# LPEM.net
KiCad netlist of a schematic drawn in EAGLE
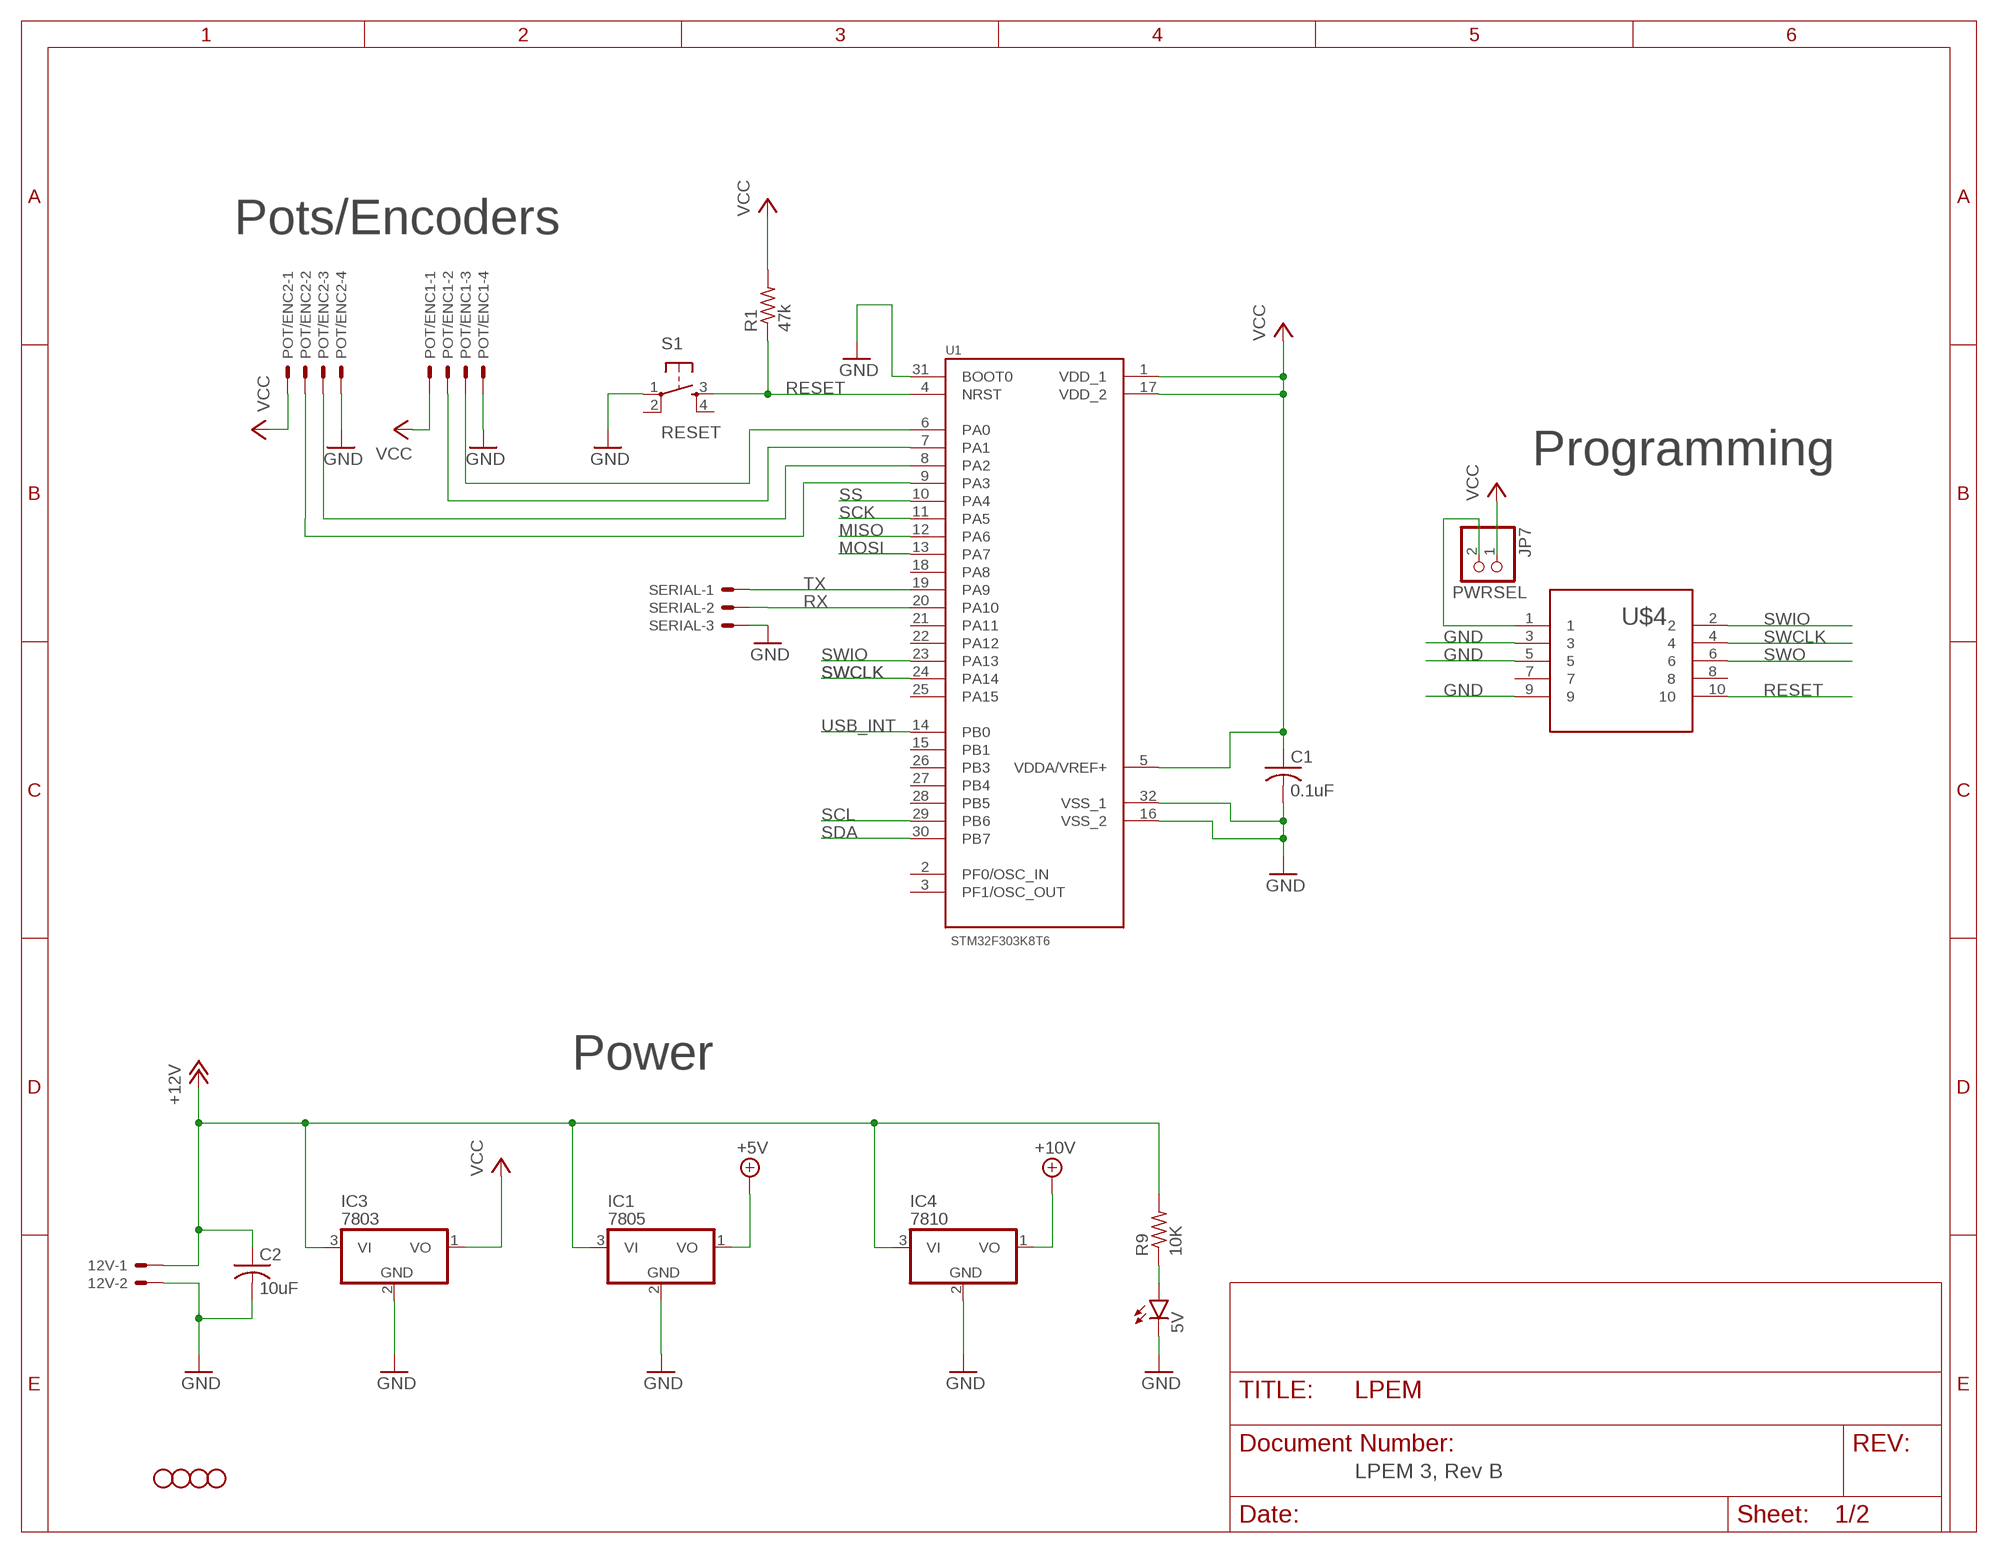
[diagram p0: schematic, sheet 1]
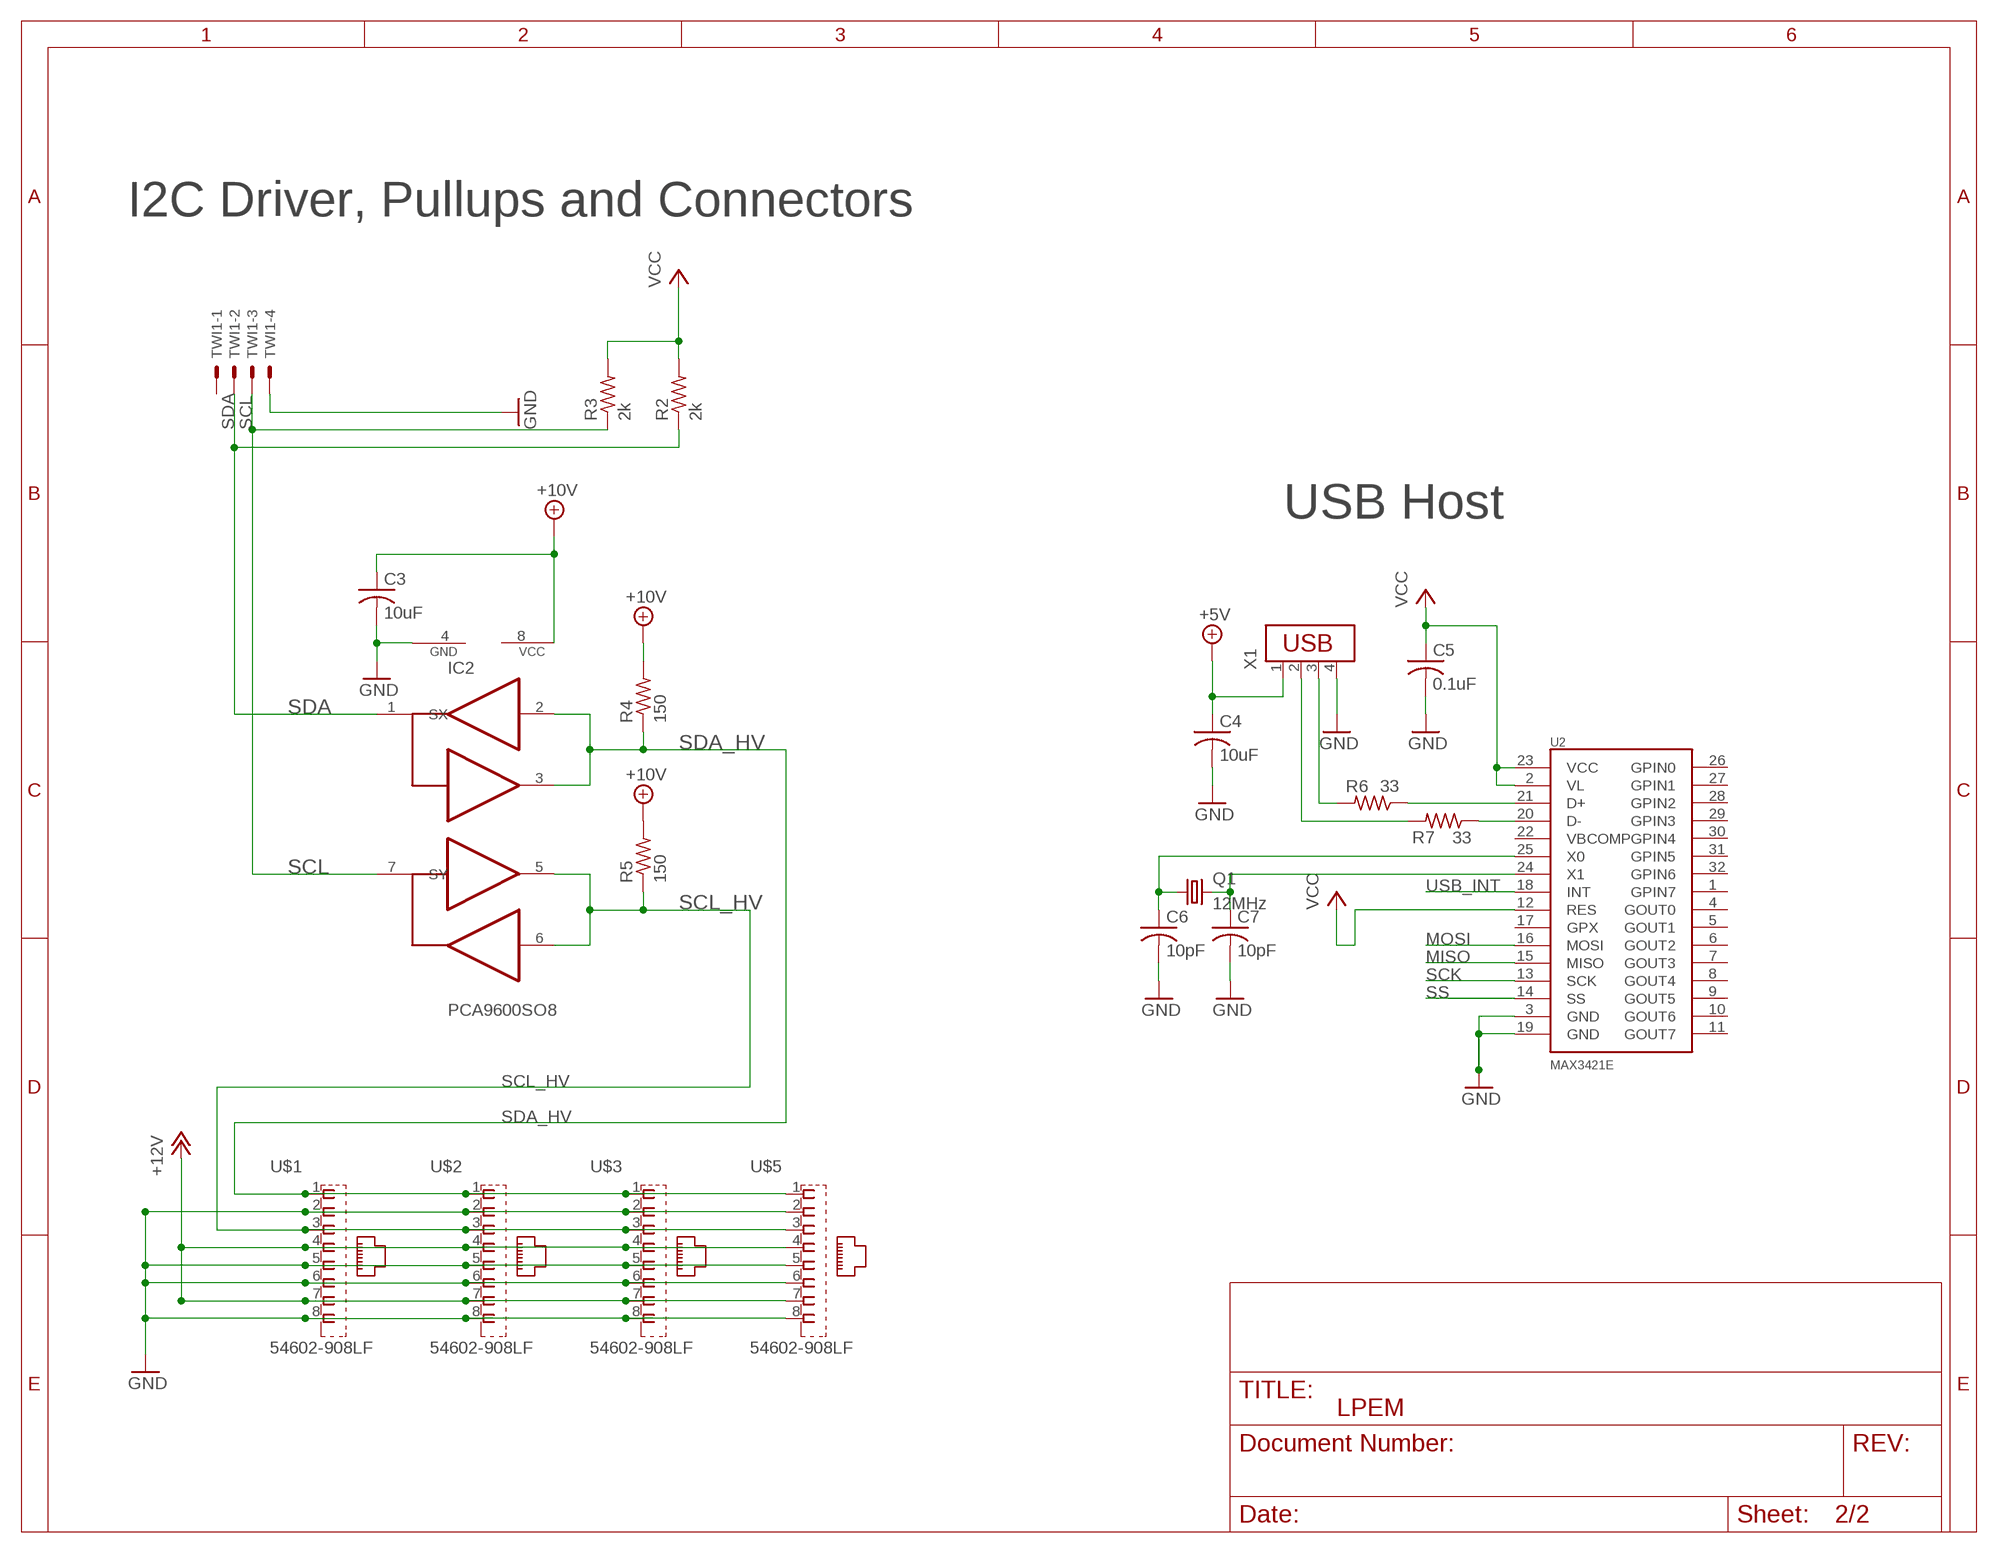
[diagram p1: schematic, sheet 2]

(export (version "E")
  (design (tool "Eeschema 10.0.6"))
  (components
    (comp (ref "C3")
      (value "10uF")
      (footprint "eagle-import:C025-025X050")
      (libsource (lib "eagle-import") (part "C-US025-025X050"))
    )
    (comp (ref "C4")
      (value "10uF")
      (footprint "eagle-import:C025-025X050")
      (libsource (lib "eagle-import") (part "C-US025-025X050"))
    )
    (comp (ref "C5")
      (value "0.1uF")
      (footprint "eagle-import:C025-025X050")
      (libsource (lib "eagle-import") (part "C-US025-025X050"))
    )
    (comp (ref "C6")
      (value "10pF")
      (footprint "eagle-import:C025-025X050")
      (libsource (lib "eagle-import") (part "C-US025-025X050"))
    )
    (comp (ref "C7")
      (value "10pF")
      (footprint "eagle-import:C025-025X050")
      (libsource (lib "eagle-import") (part "C-US025-025X050"))
    )
    (comp (ref "IC2")
      (value "PCA9600SO8")
      (footprint "eagle-import:SO08")
      (libsource (lib "eagle-import") (part "PCA9600SO8"))
    )
    (comp (ref "Q1")
      (value "12MHz")
      (footprint "eagle-import:HC18U-V")
      (libsource (lib "eagle-import") (part "CRYSTALHC18U-V"))
    )
    (comp (ref "R2")
      (value "2k")
      (footprint "eagle-import:0204_5")
      (libsource (lib "eagle-import") (part "R-US_0204/5"))
    )
    (comp (ref "R3")
      (value "2k")
      (footprint "eagle-import:0204_5")
      (libsource (lib "eagle-import") (part "R-US_0204/5"))
    )
    (comp (ref "R4")
      (value "150")
      (footprint "eagle-import:0204_5")
      (libsource (lib "eagle-import") (part "R-US_0204/5"))
    )
    (comp (ref "R5")
      (value "150")
      (footprint "eagle-import:0204_5")
      (libsource (lib "eagle-import") (part "R-US_0204/5"))
    )
    (comp (ref "R6")
      (value "33")
      (footprint "eagle-import:0204_5")
      (libsource (lib "eagle-import") (part "R-US_0204/5"))
    )
    (comp (ref "R7")
      (value "33")
      (footprint "eagle-import:0204_5")
      (libsource (lib "eagle-import") (part "R-US_0204/5"))
    )
    (comp (ref "TWI1")
      (value "22-23-2041")
      (footprint "eagle-import:22-23-2041")
      (fields (field (name "MF") "MOLEX"))
      (libsource (lib "eagle-import") (part "22-23-2041"))
    )
    (comp (ref "U$1")
      (value "54602-908LF")
      (footprint "eagle-import:AMPHENOL_54602-908LF")
      (fields (field (name "DIGI-KEY_PART_NUMBER") "609-1046-ND") (field (name "MF") "Amphenol ICC"))
      (libsource (lib "eagle-import") (part "54602-908LF"))
    )
    (comp (ref "U$2")
      (value "54602-908LF")
      (footprint "eagle-import:AMPHENOL_54602-908LF")
      (fields (field (name "DIGI-KEY_PART_NUMBER") "609-1046-ND") (field (name "MF") "Amphenol ICC"))
      (libsource (lib "eagle-import") (part "54602-908LF"))
    )
    (comp (ref "U$3")
      (value "54602-908LF")
      (footprint "eagle-import:AMPHENOL_54602-908LF")
      (fields (field (name "DIGI-KEY_PART_NUMBER") "609-1046-ND") (field (name "MF") "Amphenol ICC"))
      (libsource (lib "eagle-import") (part "54602-908LF"))
    )
    (comp (ref "U$5")
      (value "54602-908LF")
      (footprint "eagle-import:AMPHENOL_54602-908LF")
      (fields (field (name "DIGI-KEY_PART_NUMBER") "609-1046-ND") (field (name "MF") "Amphenol ICC"))
      (libsource (lib "eagle-import") (part "54602-908LF"))
    )
    (comp (ref "U2")
      (value "MAX3421E")
      (footprint "eagle-import:TQFP32-5MM")
      (fields (field (name "MF") "Maxim Integrated"))
      (libsource (lib "eagle-import") (part "MAX3421E"))
    )
    (comp (ref "X1")
      (value "USB-787616")
      (footprint "eagle-import:USB")
      (libsource (lib "eagle-import") (part "USB-787616"))
    )
    (comp (ref "5V")
      (value "LED3MM")
      (footprint "eagle-import:LED3MM")
      (libsource (lib "eagle-import") (part "LED3MM"))
    )
    (comp (ref "12V")
      (value "22-23-2021")
      (footprint "eagle-import:22-23-2021")
      (fields (field (name "MF") "MOLEX"))
      (libsource (lib "eagle-import") (part "22-23-2021"))
    )
    (comp (ref "C1")
      (value "0.1uF")
      (footprint "eagle-import:C025-025X050")
      (libsource (lib "eagle-import") (part "C-US025-025X050"))
    )
    (comp (ref "C2")
      (value "10uF")
      (footprint "eagle-import:C025-025X050")
      (libsource (lib "eagle-import") (part "C-US025-025X050"))
    )
    (comp (ref "IC1")
      (value "7805")
      (footprint "eagle-import:TO92")
      (libsource (lib "eagle-import") (part "78ZL05"))
    )
    (comp (ref "IC3")
      (value "7803")
      (footprint "eagle-import:TO92")
      (libsource (lib "eagle-import") (part "78ZL05"))
    )
    (comp (ref "IC4")
      (value "7810")
      (footprint "eagle-import:TO92")
      (libsource (lib "eagle-import") (part "78ZL05"))
    )
    (comp (ref "JP1")
      (value "STAND-OFF")
      (footprint "eagle-import:STAND-OFF")
      (libsource (lib "eagle-import") (part "STAND-OFF"))
    )
    (comp (ref "JP2")
      (value "STAND-OFF")
      (footprint "eagle-import:STAND-OFF")
      (libsource (lib "eagle-import") (part "STAND-OFF"))
    )
    (comp (ref "JP7")
      (value "PWRSEL")
      (footprint "eagle-import:1X02")
      (libsource (lib "eagle-import") (part "PINHD-1X2"))
    )
    (comp (ref "JP8")
      (value "STAND-OFF")
      (footprint "eagle-import:STAND-OFF")
      (libsource (lib "eagle-import") (part "STAND-OFF"))
    )
    (comp (ref "JP9")
      (value "STAND-OFF")
      (footprint "eagle-import:STAND-OFF")
      (libsource (lib "eagle-import") (part "STAND-OFF"))
    )
    (comp (ref "POT/ENC1")
      (value "22-23-2041")
      (footprint "eagle-import:22-23-2041")
      (fields (field (name "MF") "MOLEX"))
      (libsource (lib "eagle-import") (part "22-23-2041"))
    )
    (comp (ref "POT/ENC2")
      (value "22-23-2041")
      (footprint "eagle-import:22-23-2041")
      (fields (field (name "MF") "MOLEX"))
      (libsource (lib "eagle-import") (part "22-23-2041"))
    )
    (comp (ref "R1")
      (value "47k")
      (footprint "eagle-import:0204_5")
      (libsource (lib "eagle-import") (part "R-US_0204/5"))
    )
    (comp (ref "R9")
      (value "10K")
      (footprint "eagle-import:0204_5")
      (libsource (lib "eagle-import") (part "R-US_0204/5"))
    )
    (comp (ref "S1")
      (value "RESET")
      (footprint "eagle-import:TACTILE-PTH")
      (libsource (lib "eagle-import") (part "TAC_SWITCHPTH"))
    )
    (comp (ref "SERIAL")
      (value "22-23-2031")
      (footprint "eagle-import:22-23-2031")
      (fields (field (name "MF") "MOLEX"))
      (libsource (lib "eagle-import") (part "22-23-2031"))
    )
    (comp (ref "U$4")
      (value "CORTEX_HEADERJ")
      (footprint "eagle-import:CORTEX_HEADER")
      (fields (field (name "MF") "Samtec Inc.") (field (name "MP") "TFM-105-01-S-D-WT"))
      (libsource (lib "eagle-import") (part "CORTEX_HEADERJ"))
    )
    (comp (ref "U1")
      (value "STM32F303K8T6")
      (footprint "eagle-import:QFP80P900X900X160-32N")
      (fields (field (name "MF") "STMicroelectronics"))
      (libsource (lib "eagle-import") (part "STM32F303K8T6"))
    )
  )
  (nets
    (net (code "1") (name "+5V") (class "Default")
      (node (ref "C4") (pin "1") (pinfunction "1_1") (pintype "passive"))
      (node (ref "IC1") (pin "1") (pinfunction "VO_1") (pintype "passive"))
      (node (ref "X1") (pin "1") (pinfunction "1_1") (pintype "passive"))
    )
    (net (code "2") (name "+10V") (class "Default")
      (node (ref "C3") (pin "1") (pinfunction "1_1") (pintype "passive"))
      (node (ref "IC2") (pin "8") (pinfunction "VCC_8") (pintype "power_in"))
      (node (ref "IC4") (pin "1") (pinfunction "VO_1") (pintype "passive"))
      (node (ref "R4") (pin "2") (pinfunction "2_2") (pintype "passive"))
      (node (ref "R5") (pin "2") (pinfunction "2_2") (pintype "passive"))
    )
    (net (code "3") (name "+12V") (class "Default")
      (node (ref "12V") (pin "1") (pinfunction "S_1") (pintype "passive"))
      (node (ref "C2") (pin "1") (pinfunction "1_1") (pintype "passive"))
      (node (ref "IC1") (pin "3") (pinfunction "VI_3") (pintype "input"))
      (node (ref "IC3") (pin "3") (pinfunction "VI_3") (pintype "input"))
      (node (ref "IC4") (pin "3") (pinfunction "VI_3") (pintype "input"))
      (node (ref "R9") (pin "2") (pinfunction "2_2") (pintype "passive"))
      (node (ref "U$1") (pin "4") (pinfunction "4_4") (pintype "passive"))
      (node (ref "U$1") (pin "7") (pinfunction "7_7") (pintype "passive"))
      (node (ref "U$2") (pin "4") (pinfunction "4_4") (pintype "passive"))
      (node (ref "U$2") (pin "7") (pinfunction "7_7") (pintype "passive"))
      (node (ref "U$3") (pin "4") (pinfunction "4_4") (pintype "passive"))
      (node (ref "U$3") (pin "7") (pinfunction "7_7") (pintype "passive"))
      (node (ref "U$5") (pin "4") (pinfunction "4_4") (pintype "passive"))
      (node (ref "U$5") (pin "7") (pinfunction "7_7") (pintype "passive"))
    )
    (net (code "4") (name "GND") (class "Default")
      (node (ref "12V") (pin "2") (pinfunction "S_2") (pintype "passive"))
      (node (ref "5V") (pin "K") (pinfunction "C_K") (pintype "passive"))
      (node (ref "C1") (pin "2") (pinfunction "2_2") (pintype "passive"))
      (node (ref "C2") (pin "2") (pinfunction "2_2") (pintype "passive"))
      (node (ref "C3") (pin "2") (pinfunction "2_2") (pintype "passive"))
      (node (ref "C4") (pin "2") (pinfunction "2_2") (pintype "passive"))
      (node (ref "C5") (pin "2") (pinfunction "2_2") (pintype "passive"))
      (node (ref "C6") (pin "2") (pinfunction "2_2") (pintype "passive"))
      (node (ref "C7") (pin "2") (pinfunction "2_2") (pintype "passive"))
      (node (ref "IC1") (pin "2") (pinfunction "GND_2") (pintype "passive"))
      (node (ref "IC2") (pin "4") (pinfunction "GND_4") (pintype "power_in"))
      (node (ref "IC3") (pin "2") (pinfunction "GND_2") (pintype "passive"))
      (node (ref "IC4") (pin "2") (pinfunction "GND_2") (pintype "passive"))
      (node (ref "POT/ENC1") (pin "4") (pinfunction "S_4") (pintype "passive"))
      (node (ref "POT/ENC2") (pin "4") (pinfunction "S_4") (pintype "passive"))
      (node (ref "S1") (pin "1") (pinfunction "1_1") (pintype "passive"))
      (node (ref "SERIAL") (pin "3") (pinfunction "S_3") (pintype "passive"))
      (node (ref "TWI1") (pin "4") (pinfunction "S_4") (pintype "passive"))
      (node (ref "U$1") (pin "2") (pinfunction "2_2") (pintype "passive"))
      (node (ref "U$1") (pin "5") (pinfunction "5_5") (pintype "passive"))
      (node (ref "U$1") (pin "6") (pinfunction "6_6") (pintype "passive"))
      (node (ref "U$1") (pin "8") (pinfunction "8_8") (pintype "passive"))
      (node (ref "U$2") (pin "2") (pinfunction "2_2") (pintype "passive"))
      (node (ref "U$2") (pin "5") (pinfunction "5_5") (pintype "passive"))
      (node (ref "U$2") (pin "6") (pinfunction "6_6") (pintype "passive"))
      (node (ref "U$2") (pin "8") (pinfunction "8_8") (pintype "passive"))
      (node (ref "U$3") (pin "2") (pinfunction "2_2") (pintype "passive"))
      (node (ref "U$3") (pin "5") (pinfunction "5_5") (pintype "passive"))
      (node (ref "U$3") (pin "6") (pinfunction "6_6") (pintype "passive"))
      (node (ref "U$3") (pin "8") (pinfunction "8_8") (pintype "passive"))
      (node (ref "U$4") (pin "3") (pinfunction "3_3") (pintype "passive"))
      (node (ref "U$4") (pin "5") (pinfunction "5_5") (pintype "passive"))
      (node (ref "U$4") (pin "9") (pinfunction "9_9") (pintype "passive"))
      (node (ref "U$5") (pin "2") (pinfunction "2_2") (pintype "passive"))
      (node (ref "U$5") (pin "5") (pinfunction "5_5") (pintype "passive"))
      (node (ref "U$5") (pin "6") (pinfunction "6_6") (pintype "passive"))
      (node (ref "U$5") (pin "8") (pinfunction "8_8") (pintype "passive"))
      (node (ref "U1") (pin "16") (pinfunction "VSS_2_16") (pintype "power_in"))
      (node (ref "U1") (pin "31") (pinfunction "BOOT0_31") (pintype "input"))
      (node (ref "U1") (pin "32") (pinfunction "VSS_1_32") (pintype "power_in"))
      (node (ref "U2") (pin "19") (pinfunction "GND_19") (pintype "bidirectional"))
      (node (ref "U2") (pin "3") (pinfunction "GND_3") (pintype "bidirectional"))
      (node (ref "X1") (pin "4") (pinfunction "4_4") (pintype "passive"))
    )
    (net (code "5") (name "MISO") (class "Default")
      (node (ref "U1") (pin "12") (pinfunction "PA6_12") (pintype "bidirectional"))
      (node (ref "U2") (pin "15") (pinfunction "MISO_15") (pintype "bidirectional"))
    )
    (net (code "6") (name "MOSI") (class "Default")
      (node (ref "U1") (pin "13") (pinfunction "PA7_13") (pintype "bidirectional"))
      (node (ref "U2") (pin "16") (pinfunction "MOSI_16") (pintype "bidirectional"))
    )
    (net (code "7") (name "Net-(5V-PadA)") (class "Default")
      (node (ref "5V") (pin "A") (pinfunction "A_A") (pintype "passive"))
      (node (ref "R9") (pin "1") (pinfunction "1_1") (pintype "passive"))
    )
    (net (code "8") (name "Net-(JP7-Pad2)") (class "Default")
      (node (ref "JP7") (pin "2") (pinfunction "2_2") (pintype "passive"))
      (node (ref "U$4") (pin "1") (pinfunction "1_1") (pintype "passive"))
    )
    (net (code "9") (name "Net-(POT/ENC1B-S)") (class "Default")
      (node (ref "POT/ENC1") (pin "2") (pinfunction "S_2") (pintype "passive"))
      (node (ref "U1") (pin "7") (pinfunction "PA1_7") (pintype "bidirectional"))
    )
    (net (code "10") (name "Net-(POT/ENC1C-S)") (class "Default")
      (node (ref "POT/ENC1") (pin "3") (pinfunction "S_3") (pintype "passive"))
      (node (ref "U1") (pin "6") (pinfunction "PA0_6") (pintype "bidirectional"))
    )
    (net (code "11") (name "Net-(POT/ENC2B-S)") (class "Default")
      (node (ref "POT/ENC2") (pin "2") (pinfunction "S_2") (pintype "passive"))
      (node (ref "U1") (pin "9") (pinfunction "PA3_9") (pintype "bidirectional"))
    )
    (net (code "12") (name "Net-(POT/ENC2C-S)") (class "Default")
      (node (ref "POT/ENC2") (pin "3") (pinfunction "S_3") (pintype "passive"))
      (node (ref "U1") (pin "8") (pinfunction "PA2_8") (pintype "bidirectional"))
    )
    (net (code "13") (name "Net-(R6-Pad2)") (class "Default")
      (node (ref "R6") (pin "2") (pinfunction "2_2") (pintype "passive"))
      (node (ref "X1") (pin "3") (pinfunction "3_3") (pintype "passive"))
    )
    (net (code "14") (name "Net-(R7-Pad2)") (class "Default")
      (node (ref "R7") (pin "2") (pinfunction "2_2") (pintype "passive"))
      (node (ref "X1") (pin "2") (pinfunction "2_2") (pintype "passive"))
    )
    (net (code "15") (name "Net-(U2-D+)") (class "Default")
      (node (ref "R6") (pin "1") (pinfunction "1_1") (pintype "passive"))
      (node (ref "U2") (pin "21") (pinfunction "D+_21") (pintype "bidirectional"))
    )
    (net (code "16") (name "Net-(U2-D-)") (class "Default")
      (node (ref "R7") (pin "1") (pinfunction "1_1") (pintype "passive"))
      (node (ref "U2") (pin "20") (pinfunction "D-_20") (pintype "bidirectional"))
    )
    (net (code "17") (name "Net-(U2-X0)") (class "Default")
      (node (ref "C6") (pin "1") (pinfunction "1_1") (pintype "passive"))
      (node (ref "Q1") (pin "1") (pinfunction "1_1") (pintype "passive"))
      (node (ref "U2") (pin "25") (pinfunction "X0_25") (pintype "bidirectional"))
    )
    (net (code "18") (name "Net-(U2-X1)") (class "Default")
      (node (ref "C7") (pin "1") (pinfunction "1_1") (pintype "passive"))
      (node (ref "Q1") (pin "2") (pinfunction "2_2") (pintype "passive"))
      (node (ref "U2") (pin "24") (pinfunction "X1_24") (pintype "bidirectional"))
    )
    (net (code "19") (name "RESET") (class "Default")
      (node (ref "R1") (pin "1") (pinfunction "1_1") (pintype "passive"))
      (node (ref "S1") (pin "3") (pinfunction "3_3") (pintype "passive"))
      (node (ref "U$4") (pin "10") (pinfunction "10_10") (pintype "passive"))
      (node (ref "U1") (pin "4") (pinfunction "NRST_4") (pintype "bidirectional"))
    )
    (net (code "20") (name "RX") (class "Default")
      (node (ref "SERIAL") (pin "2") (pinfunction "S_2") (pintype "passive"))
      (node (ref "U1") (pin "20") (pinfunction "PA10_20") (pintype "bidirectional"))
    )
    (net (code "21") (name "SCK") (class "Default")
      (node (ref "U1") (pin "11") (pinfunction "PA5_11") (pintype "bidirectional"))
      (node (ref "U2") (pin "13") (pinfunction "SCK_13") (pintype "bidirectional"))
    )
    (net (code "22") (name "SCL") (class "Default")
      (node (ref "IC2") (pin "7") (pinfunction "SY_7") (pintype "bidirectional"))
      (node (ref "R3") (pin "1") (pinfunction "1_1") (pintype "passive"))
      (node (ref "TWI1") (pin "3") (pinfunction "S_3") (pintype "passive"))
      (node (ref "U1") (pin "29") (pinfunction "PB6_29") (pintype "bidirectional"))
    )
    (net (code "23") (name "SCL_HV") (class "Default")
      (node (ref "IC2") (pin "5") (pinfunction "TY_5") (pintype "output"))
      (node (ref "IC2") (pin "6") (pinfunction "RY_6") (pintype "input"))
      (node (ref "R5") (pin "1") (pinfunction "1_1") (pintype "passive"))
      (node (ref "U$1") (pin "3") (pinfunction "3_3") (pintype "passive"))
      (node (ref "U$2") (pin "3") (pinfunction "3_3") (pintype "passive"))
      (node (ref "U$3") (pin "3") (pinfunction "3_3") (pintype "passive"))
      (node (ref "U$5") (pin "3") (pinfunction "3_3") (pintype "passive"))
    )
    (net (code "24") (name "SDA") (class "Default")
      (node (ref "IC2") (pin "1") (pinfunction "SX_1") (pintype "bidirectional"))
      (node (ref "R2") (pin "1") (pinfunction "1_1") (pintype "passive"))
      (node (ref "TWI1") (pin "2") (pinfunction "S_2") (pintype "passive"))
      (node (ref "U1") (pin "30") (pinfunction "PB7_30") (pintype "bidirectional"))
    )
    (net (code "25") (name "SDA_HV") (class "Default")
      (node (ref "IC2") (pin "2") (pinfunction "RX_2") (pintype "input"))
      (node (ref "IC2") (pin "3") (pinfunction "TX_3") (pintype "output"))
      (node (ref "R4") (pin "1") (pinfunction "1_1") (pintype "passive"))
      (node (ref "U$1") (pin "1") (pinfunction "1_1") (pintype "passive"))
      (node (ref "U$2") (pin "1") (pinfunction "1_1") (pintype "passive"))
      (node (ref "U$3") (pin "1") (pinfunction "1_1") (pintype "passive"))
      (node (ref "U$5") (pin "1") (pinfunction "1_1") (pintype "passive"))
    )
    (net (code "26") (name "SS") (class "Default")
      (node (ref "U1") (pin "10") (pinfunction "PA4_10") (pintype "bidirectional"))
      (node (ref "U2") (pin "14") (pinfunction "SS_14") (pintype "bidirectional"))
    )
    (net (code "27") (name "SWCLK") (class "Default")
      (node (ref "U$4") (pin "4") (pinfunction "4_4") (pintype "passive"))
      (node (ref "U1") (pin "24") (pinfunction "PA14_24") (pintype "bidirectional"))
    )
    (net (code "28") (name "SWIO") (class "Default")
      (node (ref "U$4") (pin "2") (pinfunction "2_2") (pintype "passive"))
      (node (ref "U1") (pin "23") (pinfunction "PA13_23") (pintype "bidirectional"))
    )
    (net (code "29") (name "SWO") (class "Default")
      (node (ref "U$4") (pin "6") (pinfunction "6_6") (pintype "passive"))
    )
    (net (code "30") (name "TX") (class "Default")
      (node (ref "SERIAL") (pin "1") (pinfunction "S_1") (pintype "passive"))
      (node (ref "U1") (pin "19") (pinfunction "PA9_19") (pintype "bidirectional"))
    )
    (net (code "31") (name "USB_INT") (class "Default")
      (node (ref "U1") (pin "14") (pinfunction "PB0_14") (pintype "bidirectional"))
      (node (ref "U2") (pin "18") (pinfunction "INT_18") (pintype "bidirectional"))
    )
    (net (code "32") (name "VCC") (class "Default")
      (node (ref "C1") (pin "1") (pinfunction "1_1") (pintype "passive"))
      (node (ref "C5") (pin "1") (pinfunction "1_1") (pintype "passive"))
      (node (ref "IC3") (pin "1") (pinfunction "VO_1") (pintype "passive"))
      (node (ref "JP7") (pin "1") (pinfunction "1_1") (pintype "passive"))
      (node (ref "POT/ENC1") (pin "1") (pinfunction "S_1") (pintype "passive"))
      (node (ref "POT/ENC2") (pin "1") (pinfunction "S_1") (pintype "passive"))
      (node (ref "R1") (pin "2") (pinfunction "2_2") (pintype "passive"))
      (node (ref "R2") (pin "2") (pinfunction "2_2") (pintype "passive"))
      (node (ref "R3") (pin "2") (pinfunction "2_2") (pintype "passive"))
      (node (ref "U1") (pin "1") (pinfunction "VDD_1_1") (pintype "power_in"))
      (node (ref "U1") (pin "17") (pinfunction "VDD_2_17") (pintype "power_in"))
      (node (ref "U1") (pin "5") (pinfunction "VDDA/VREF+_5") (pintype "power_in"))
      (node (ref "U2") (pin "12") (pinfunction "RES_12") (pintype "bidirectional"))
      (node (ref "U2") (pin "2") (pinfunction "VL_2") (pintype "bidirectional"))
      (node (ref "U2") (pin "23") (pinfunction "VCC_23") (pintype "bidirectional"))
    )
    (net (code "33") (name "unconnected-(S1-Pad2)") (class "Default")
      (node (ref "S1") (pin "2") (pinfunction "2_2") (pintype "passive"))
    )
    (net (code "34") (name "unconnected-(S1-Pad4)") (class "Default")
      (node (ref "S1") (pin "4") (pinfunction "4_4") (pintype "passive"))
    )
    (net (code "35") (name "unconnected-(TWI1A-S-Pad1)") (class "Default")
      (node (ref "TWI1") (pin "1") (pinfunction "S_1") (pintype "passive"))
    )
    (net (code "36") (name "unconnected-(U$4-Pad7)") (class "Default")
      (node (ref "U$4") (pin "7") (pinfunction "7_7") (pintype "passive"))
    )
    (net (code "37") (name "unconnected-(U$4-Pad8)") (class "Default")
      (node (ref "U$4") (pin "8") (pinfunction "8_8") (pintype "passive"))
    )
    (net (code "38") (name "unconnected-(U1-PA8-Pad18)") (class "Default")
      (node (ref "U1") (pin "18") (pinfunction "PA8_18") (pintype "bidirectional"))
    )
    (net (code "39") (name "unconnected-(U1-PA11-Pad21)") (class "Default")
      (node (ref "U1") (pin "21") (pinfunction "PA11_21") (pintype "bidirectional"))
    )
    (net (code "40") (name "unconnected-(U1-PA12-Pad22)") (class "Default")
      (node (ref "U1") (pin "22") (pinfunction "PA12_22") (pintype "bidirectional"))
    )
    (net (code "41") (name "unconnected-(U1-PA15-Pad25)") (class "Default")
      (node (ref "U1") (pin "25") (pinfunction "PA15_25") (pintype "bidirectional"))
    )
    (net (code "42") (name "unconnected-(U1-PB1-Pad15)") (class "Default")
      (node (ref "U1") (pin "15") (pinfunction "PB1_15") (pintype "bidirectional"))
    )
    (net (code "43") (name "unconnected-(U1-PB3-Pad26)") (class "Default")
      (node (ref "U1") (pin "26") (pinfunction "PB3_26") (pintype "bidirectional"))
    )
    (net (code "44") (name "unconnected-(U1-PB4-Pad27)") (class "Default")
      (node (ref "U1") (pin "27") (pinfunction "PB4_27") (pintype "bidirectional"))
    )
    (net (code "45") (name "unconnected-(U1-PB5-Pad28)") (class "Default")
      (node (ref "U1") (pin "28") (pinfunction "PB5_28") (pintype "bidirectional"))
    )
    (net (code "46") (name "unconnected-(U1-PF0{slash}OSC_IN-Pad2)") (class "Default")
      (node (ref "U1") (pin "2") (pinfunction "PF0/OSC_IN_2") (pintype "bidirectional"))
    )
    (net (code "47") (name "unconnected-(U1-PF1{slash}OSC_OUT-Pad3)") (class "Default")
      (node (ref "U1") (pin "3") (pinfunction "PF1/OSC_OUT_3") (pintype "bidirectional"))
    )
    (net (code "48") (name "unconnected-(U2-GOUT0-Pad4)") (class "Default")
      (node (ref "U2") (pin "4") (pinfunction "GOUT0_4") (pintype "bidirectional"))
    )
    (net (code "49") (name "unconnected-(U2-GOUT1-Pad5)") (class "Default")
      (node (ref "U2") (pin "5") (pinfunction "GOUT1_5") (pintype "bidirectional"))
    )
    (net (code "50") (name "unconnected-(U2-GOUT2-Pad6)") (class "Default")
      (node (ref "U2") (pin "6") (pinfunction "GOUT2_6") (pintype "bidirectional"))
    )
    (net (code "51") (name "unconnected-(U2-GOUT3-Pad7)") (class "Default")
      (node (ref "U2") (pin "7") (pinfunction "GOUT3_7") (pintype "bidirectional"))
    )
    (net (code "52") (name "unconnected-(U2-GOUT4-Pad8)") (class "Default")
      (node (ref "U2") (pin "8") (pinfunction "GOUT4_8") (pintype "bidirectional"))
    )
    (net (code "53") (name "unconnected-(U2-GOUT5-Pad9)") (class "Default")
      (node (ref "U2") (pin "9") (pinfunction "GOUT5_9") (pintype "bidirectional"))
    )
    (net (code "54") (name "unconnected-(U2-GOUT6-Pad10)") (class "Default")
      (node (ref "U2") (pin "10") (pinfunction "GOUT6_10") (pintype "bidirectional"))
    )
    (net (code "55") (name "unconnected-(U2-GOUT7-Pad11)") (class "Default")
      (node (ref "U2") (pin "11") (pinfunction "GOUT7_11") (pintype "bidirectional"))
    )
    (net (code "56") (name "unconnected-(U2-GPIN0-Pad26)") (class "Default")
      (node (ref "U2") (pin "26") (pinfunction "GPIN0_26") (pintype "bidirectional"))
    )
    (net (code "57") (name "unconnected-(U2-GPIN1-Pad27)") (class "Default")
      (node (ref "U2") (pin "27") (pinfunction "GPIN1_27") (pintype "bidirectional"))
    )
    (net (code "58") (name "unconnected-(U2-GPIN2-Pad28)") (class "Default")
      (node (ref "U2") (pin "28") (pinfunction "GPIN2_28") (pintype "bidirectional"))
    )
    (net (code "59") (name "unconnected-(U2-GPIN3-Pad29)") (class "Default")
      (node (ref "U2") (pin "29") (pinfunction "GPIN3_29") (pintype "bidirectional"))
    )
    (net (code "60") (name "unconnected-(U2-GPIN4-Pad30)") (class "Default")
      (node (ref "U2") (pin "30") (pinfunction "GPIN4_30") (pintype "bidirectional"))
    )
    (net (code "61") (name "unconnected-(U2-GPIN5-Pad31)") (class "Default")
      (node (ref "U2") (pin "31") (pinfunction "GPIN5_31") (pintype "bidirectional"))
    )
    (net (code "62") (name "unconnected-(U2-GPIN6-Pad32)") (class "Default")
      (node (ref "U2") (pin "32") (pinfunction "GPIN6_32") (pintype "bidirectional"))
    )
    (net (code "63") (name "unconnected-(U2-GPIN7-Pad1)") (class "Default")
      (node (ref "U2") (pin "1") (pinfunction "GPIN7_1") (pintype "bidirectional"))
    )
    (net (code "64") (name "unconnected-(U2-GPX-Pad17)") (class "Default")
      (node (ref "U2") (pin "17") (pinfunction "GPX_17") (pintype "bidirectional"))
    )
    (net (code "65") (name "unconnected-(U2-VBCOMP-Pad22)") (class "Default")
      (node (ref "U2") (pin "22") (pinfunction "VBCOMP_22") (pintype "bidirectional"))
    )
  )
)
